# 1-Schematic_INFRARED_WAVER_V0_CHEAP.net
KiCad netlist of a schematic drawn in EasyEDA
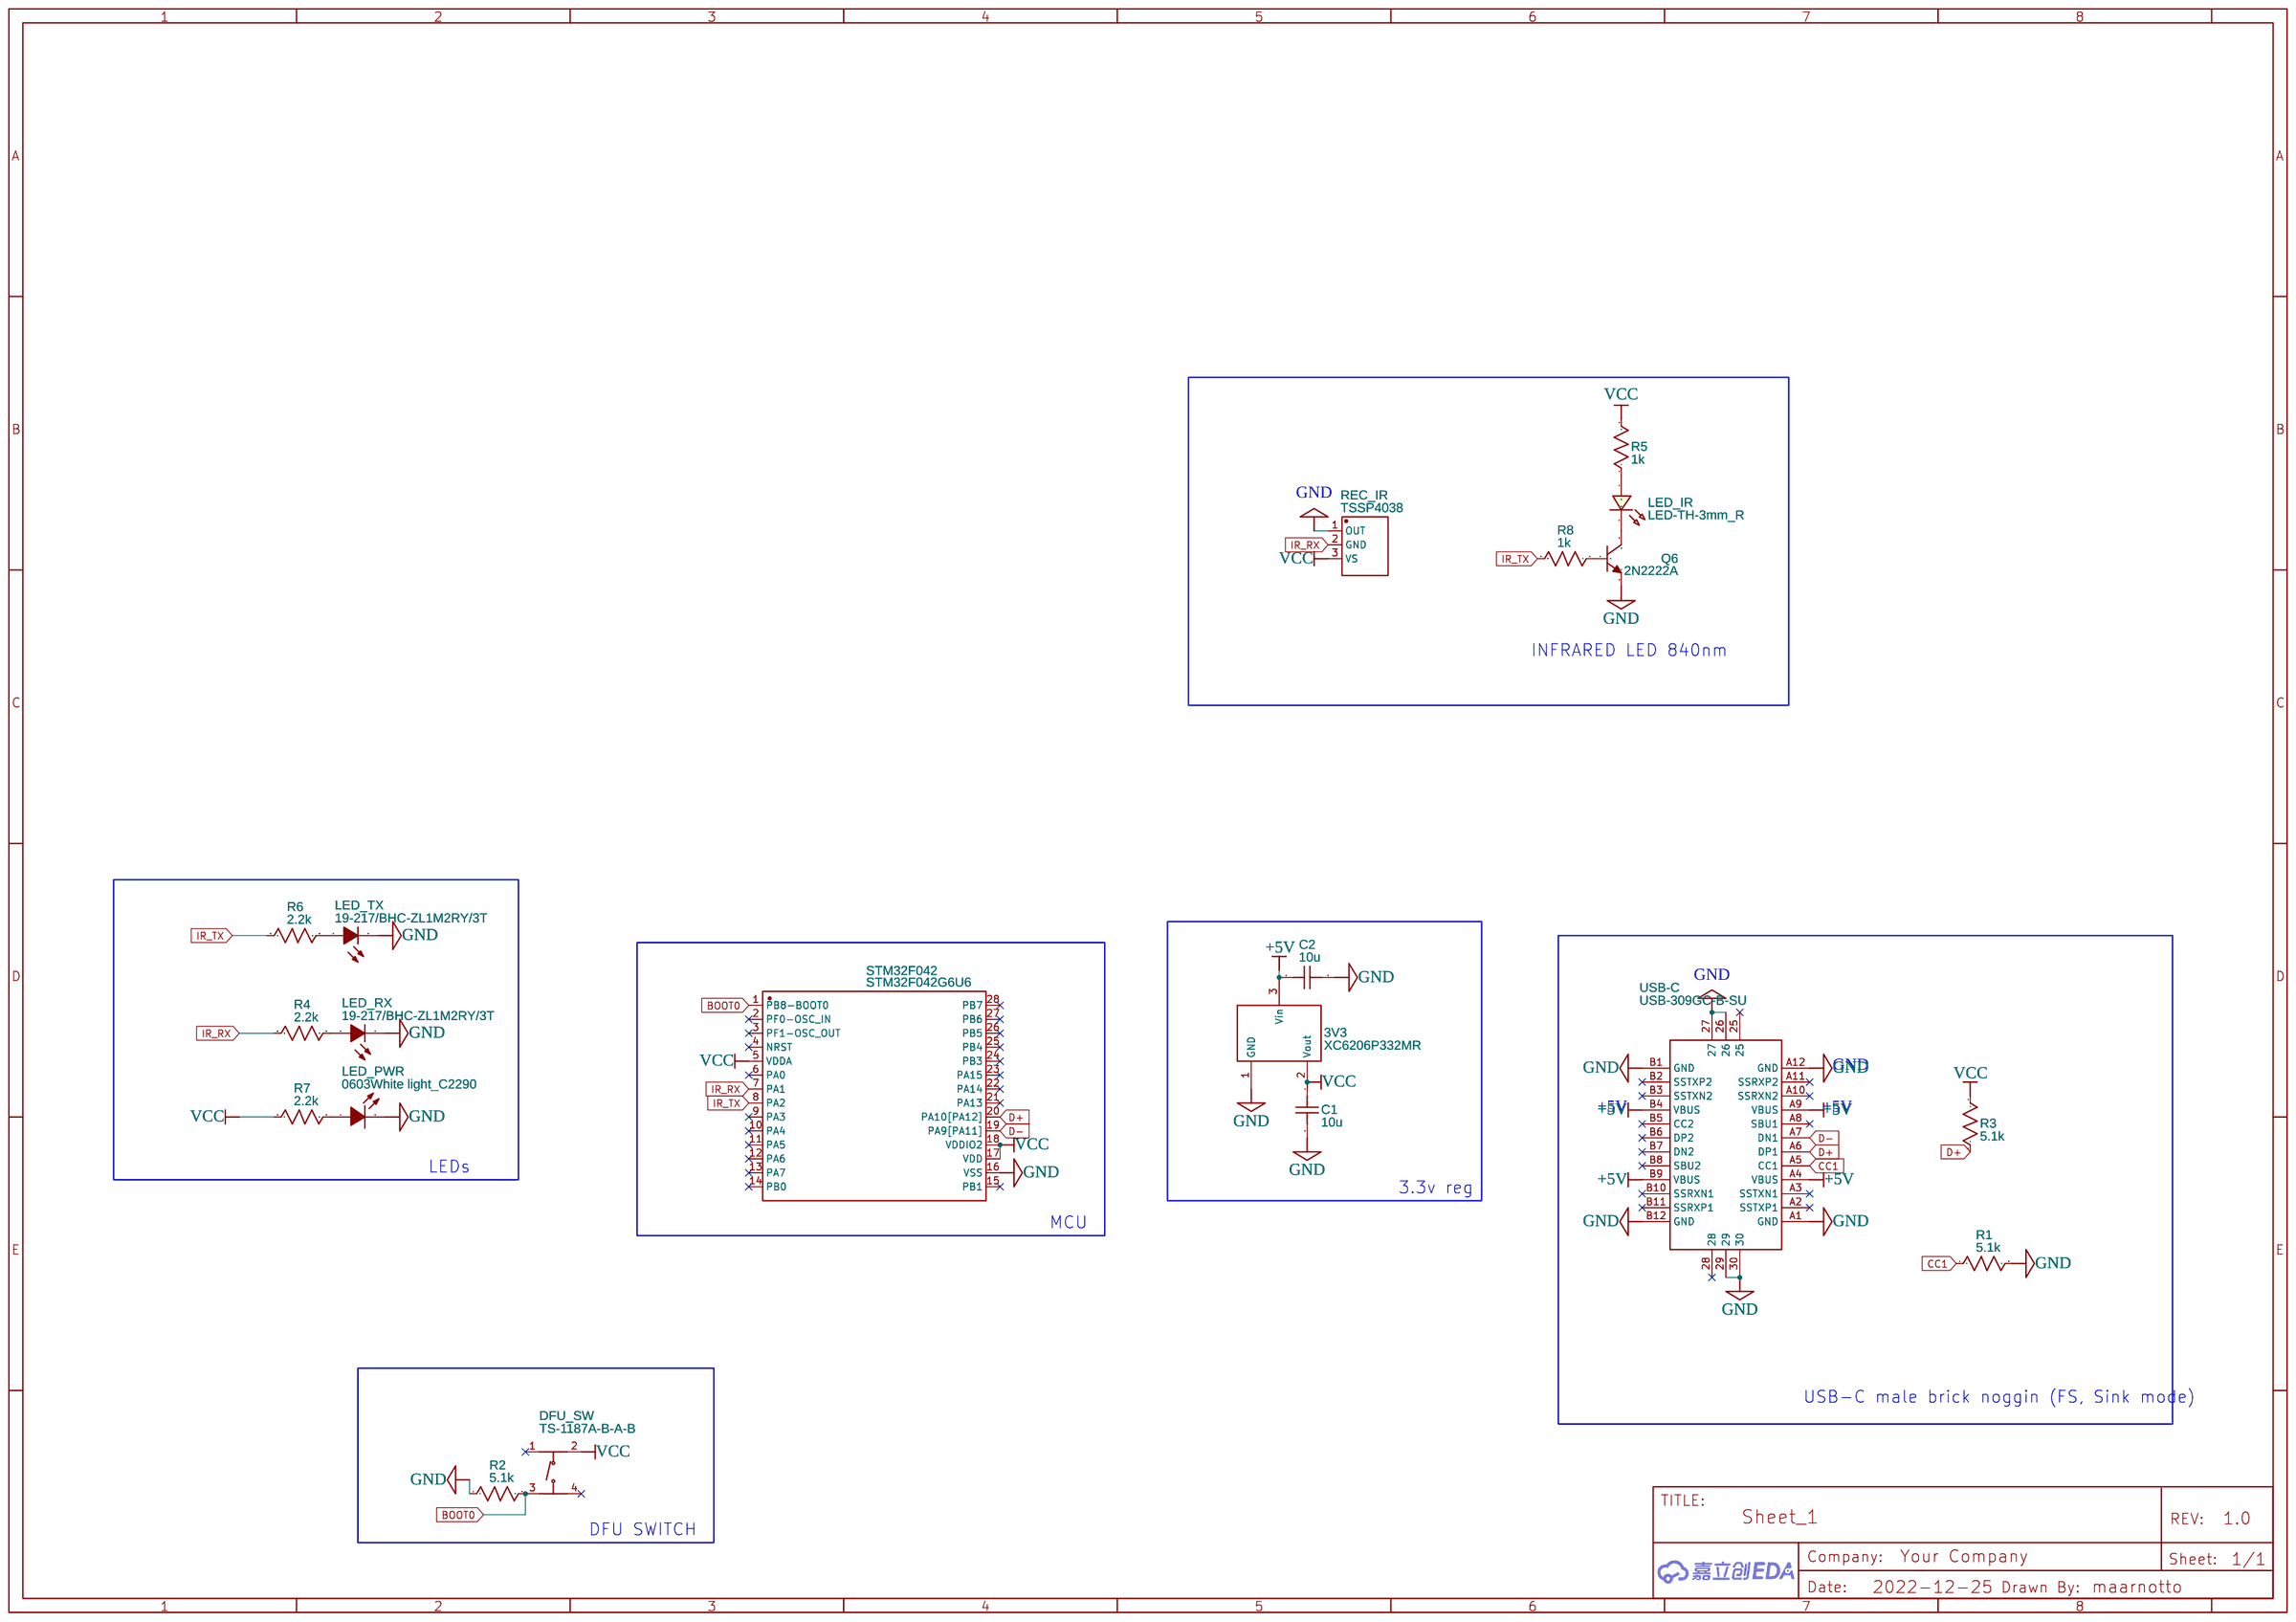
[diagram p0: schematic sheet]

(export (version "E")
  (design (tool "Eeschema 10.0.6"))
  (components
    (comp (ref "3V3")
      (value "XC6206P332MR")
      (fields (field (name "Manufacturer") "TOREX(特瑞仕)"))
      (libsource (lib "") (part "XC6206P332MR"))
    )
    (comp (ref "C1") (value "10u") (libsource (lib "") (part "C_0603_US")))
    (comp (ref "C2") (value "10u") (libsource (lib "") (part "C_0603_US_1")))
    (comp (ref "DFU_SW")
      (value "TS-1187A-B-A-B")
      (fields (field (name "Manufacturer") "XKB Connectivity(中国星坤)"))
      (libsource (lib "") (part "TS-1187A-B-A-B"))
    )
    (comp (ref "LED_IR")
      (value "LED-TH-3mm_R")
      (fields
        (field (name "Manufacturer Part") "204-10SDRD/S530-A3-L")
        (field (name "Manufacturer") "EVERLIGHT(台湾亿光)")
      )
      (libsource (lib "") (part "LED-TH-3mm_R"))
    )
    (comp (ref "LED_PWR")
      (value "0603White light_C2290")
      (fields (field (name "Manufacturer Part") "KT-0603白灯"))
      (libsource (lib "") (part "0603White light_C2290"))
    )
    (comp (ref "LED_RX")
      (value "19-217/BHC-ZL1M2RY/3T")
      (fields (field (name "Manufacturer") "EVERLIGHT(亿光)"))
      (libsource (lib "") (part "19-217/BHC-ZL1M2RY/3T_1"))
    )
    (comp (ref "LED_TX")
      (value "19-217/BHC-ZL1M2RY/3T")
      (fields (field (name "Manufacturer") "EVERLIGHT(亿光)"))
      (libsource (lib "") (part "19-217/BHC-ZL1M2RY/3T"))
    )
    (comp (ref "Q6")
      (value "2N2222A")
      (fields (field (name "Manufacturer") "BLUE ROCKET(蓝箭)"))
      (libsource (lib "") (part "2N2222A"))
    )
    (comp (ref "R1") (value "5.1k") (libsource (lib "") (part "R_0603_US")))
    (comp (ref "R2") (value "5.1k") (libsource (lib "") (part "R_0603_US")))
    (comp (ref "R3") (value "5.1k") (libsource (lib "") (part "R_0603_US_1")))
    (comp (ref "R4") (value "2.2k") (libsource (lib "") (part "R_0603_US")))
    (comp (ref "R5") (value "1k") (libsource (lib "") (part "R_AXIAL-0.3_US")))
    (comp (ref "R6") (value "2.2k") (libsource (lib "") (part "R_0603_US")))
    (comp (ref "R7") (value "2.2k") (libsource (lib "") (part "R_0603_US")))
    (comp (ref "R8") (value "1k") (libsource (lib "") (part "R_AXIAL-0.3_US_1")))
    (comp (ref "REC_IR")
      (value "TSSP4038")
      (fields (field (name "Manufacturer") "VISHAY(威世)"))
      (libsource (lib "") (part "TSSP4038"))
    )
    (comp (ref "STM32F042")
      (value "STM32F042G6U6")
      (fields (field (name "Manufacturer") "ST(意法半导体)"))
      (libsource (lib "") (part "STM32F042G6U6"))
    )
    (comp (ref "USB-C")
      (value "USB-309GC-B-SU")
      (fields (field (name "Manufacturer") "HOOYA"))
      (libsource (lib "") (part "USB-309GC-B-SU"))
    )
  )
  (nets
    (net (code "1") (name "+5V") (class "Default")
      (node (ref "3V3") (pin "3") (pinfunction "Vin_3") (pintype "unspecified"))
      (node (ref "C2") (pin "2") (pinfunction "2_2") (pintype "unspecified"))
      (node (ref "USB-C") (pin "A4") (pinfunction "VBUS_A4") (pintype "unspecified"))
      (node (ref "USB-C") (pin "A9") (pinfunction "VBUS_A9") (pintype "unspecified"))
      (node (ref "USB-C") (pin "B4") (pinfunction "VBUS_B4") (pintype "unspecified"))
      (node (ref "USB-C") (pin "B9") (pinfunction "VBUS_B9") (pintype "unspecified"))
    )
    (net (code "2") (name "BOOT0") (class "Default")
      (node (ref "DFU_SW") (pin "3") (pinfunction "C_3") (pintype "unspecified"))
      (node (ref "R2") (pin "2") (pinfunction "2_2") (pintype "unspecified"))
      (node (ref "STM32F042") (pin "1") (pinfunction "PB8-BOOT0_1") (pintype "unspecified"))
    )
    (net (code "3") (name "CC1") (class "Default")
      (node (ref "R1") (pin "1") (pinfunction "1_1") (pintype "unspecified"))
      (node (ref "USB-C") (pin "A5") (pinfunction "CC1_A5") (pintype "unspecified"))
    )
    (net (code "4") (name "D+") (class "Default")
      (node (ref "R3") (pin "2") (pinfunction "2_2") (pintype "unspecified"))
      (node (ref "STM32F042") (pin "20") (pinfunction "PA10[PA12]_20") (pintype "unspecified"))
      (node (ref "USB-C") (pin "A6") (pinfunction "DP1_A6") (pintype "unspecified"))
    )
    (net (code "5") (name "D-") (class "Default")
      (node (ref "STM32F042") (pin "19") (pinfunction "PA9[PA11]_19") (pintype "unspecified"))
      (node (ref "USB-C") (pin "A7") (pinfunction "DN1_A7") (pintype "unspecified"))
    )
    (net (code "6") (name "GND") (class "Default")
      (node (ref "3V3") (pin "1") (pinfunction "GND_1") (pintype "unspecified"))
      (node (ref "C1") (pin "2") (pinfunction "2_2") (pintype "unspecified"))
      (node (ref "C2") (pin "1") (pinfunction "1_1") (pintype "unspecified"))
      (node (ref "LED_PWR") (pin "2") (pinfunction "K_2") (pintype "unspecified"))
      (node (ref "LED_RX") (pin "1") (pinfunction "C_1") (pintype "input"))
      (node (ref "LED_TX") (pin "1") (pinfunction "C_1") (pintype "input"))
      (node (ref "Q6") (pin "3") (pinfunction "E_3") (pintype "unspecified"))
      (node (ref "R1") (pin "2") (pinfunction "2_2") (pintype "unspecified"))
      (node (ref "R2") (pin "1") (pinfunction "1_1") (pintype "unspecified"))
      (node (ref "REC_IR") (pin "1") (pinfunction "OUT_1") (pintype "unspecified"))
      (node (ref "STM32F042") (pin "16") (pinfunction "VSS_16") (pintype "unspecified"))
      (node (ref "USB-C") (pin "26") (pinfunction "26_26") (pintype "unspecified"))
      (node (ref "USB-C") (pin "27") (pinfunction "27_27") (pintype "unspecified"))
      (node (ref "USB-C") (pin "29") (pinfunction "29_29") (pintype "unspecified"))
      (node (ref "USB-C") (pin "30") (pinfunction "30_30") (pintype "unspecified"))
      (node (ref "USB-C") (pin "A1") (pinfunction "GND_A1") (pintype "unspecified"))
      (node (ref "USB-C") (pin "A12") (pinfunction "GND_A12") (pintype "unspecified"))
      (node (ref "USB-C") (pin "B1") (pinfunction "GND_B1") (pintype "unspecified"))
      (node (ref "USB-C") (pin "B12") (pinfunction "GND_B12") (pintype "unspecified"))
    )
    (net (code "7") (name "IR_RX") (class "Default")
      (node (ref "R4") (pin "1") (pinfunction "1_1") (pintype "unspecified"))
      (node (ref "REC_IR") (pin "2") (pinfunction "GND_2") (pintype "unspecified"))
      (node (ref "STM32F042") (pin "7") (pinfunction "PA1_7") (pintype "unspecified"))
    )
    (net (code "8") (name "IR_TX") (class "Default")
      (node (ref "R6") (pin "1") (pinfunction "1_1") (pintype "unspecified"))
      (node (ref "R8") (pin "2") (pinfunction "2_2") (pintype "unspecified"))
      (node (ref "STM32F042") (pin "8") (pinfunction "PA2_8") (pintype "unspecified"))
    )
    (net (code "9") (name "Net-(LED_IR-Pad1)") (class "Default")
      (node (ref "LED_IR") (pin "1") (pinfunction "1_1") (pintype "unspecified"))
      (node (ref "R5") (pin "1") (pinfunction "1_1") (pintype "unspecified"))
    )
    (net (code "10") (name "Net-(LED_PWR-A)") (class "Default")
      (node (ref "LED_PWR") (pin "1") (pinfunction "A_1") (pintype "unspecified"))
      (node (ref "R7") (pin "2") (pinfunction "2_2") (pintype "unspecified"))
    )
    (net (code "11") (name "Net-(LED_RX-A)") (class "Default")
      (node (ref "LED_RX") (pin "2") (pinfunction "A_2") (pintype "input"))
      (node (ref "R4") (pin "2") (pinfunction "2_2") (pintype "unspecified"))
    )
    (net (code "12") (name "Net-(LED_TX-A)") (class "Default")
      (node (ref "LED_TX") (pin "2") (pinfunction "A_2") (pintype "input"))
      (node (ref "R6") (pin "2") (pinfunction "2_2") (pintype "unspecified"))
    )
    (net (code "13") (name "Net-(Q6-B)") (class "Default")
      (node (ref "Q6") (pin "2") (pinfunction "B_2") (pintype "unspecified"))
      (node (ref "R8") (pin "1") (pinfunction "1_1") (pintype "unspecified"))
    )
    (net (code "14") (name "Net-(Q6-C)") (class "Default")
      (node (ref "LED_IR") (pin "2") (pinfunction "2_2") (pintype "unspecified"))
      (node (ref "Q6") (pin "1") (pinfunction "C_1") (pintype "unspecified"))
    )
    (net (code "15") (name "VCC") (class "Default")
      (node (ref "3V3") (pin "2") (pinfunction "Vout_2") (pintype "unspecified"))
      (node (ref "C1") (pin "1") (pinfunction "1_1") (pintype "unspecified"))
      (node (ref "DFU_SW") (pin "2") (pinfunction "B_2") (pintype "unspecified"))
      (node (ref "R3") (pin "1") (pinfunction "1_1") (pintype "unspecified"))
      (node (ref "R5") (pin "2") (pinfunction "2_2") (pintype "unspecified"))
      (node (ref "R7") (pin "1") (pinfunction "1_1") (pintype "unspecified"))
      (node (ref "REC_IR") (pin "3") (pinfunction "VS_3") (pintype "unspecified"))
      (node (ref "STM32F042") (pin "17") (pinfunction "VDD_17") (pintype "unspecified"))
      (node (ref "STM32F042") (pin "18") (pinfunction "VDDIO2_18") (pintype "unspecified"))
      (node (ref "STM32F042") (pin "5") (pinfunction "VDDA_5") (pintype "unspecified"))
    )
    (net (code "16") (name "unconnected-(DFU_SW-A-Pad1)") (class "Default")
      (node (ref "DFU_SW") (pin "1") (pinfunction "A_1") (pintype "unspecified+no_connect"))
    )
    (net (code "17") (name "unconnected-(DFU_SW-D-Pad4)") (class "Default")
      (node (ref "DFU_SW") (pin "4") (pinfunction "D_4") (pintype "unspecified+no_connect"))
    )
    (net (code "18") (name "unconnected-(STM32F042-NRST-Pad4)") (class "Default")
      (node (ref "STM32F042") (pin "4") (pinfunction "NRST_4") (pintype "unspecified+no_connect"))
    )
    (net (code "19") (name "unconnected-(STM32F042-PA0-Pad6)") (class "Default")
      (node (ref "STM32F042") (pin "6") (pinfunction "PA0_6") (pintype "unspecified+no_connect"))
    )
    (net (code "20") (name "unconnected-(STM32F042-PA3-Pad9)") (class "Default")
      (node (ref "STM32F042") (pin "9") (pinfunction "PA3_9") (pintype "unspecified+no_connect"))
    )
    (net (code "21") (name "unconnected-(STM32F042-PA4-Pad10)") (class "Default")
      (node (ref "STM32F042") (pin "10") (pinfunction "PA4_10") (pintype "unspecified+no_connect"))
    )
    (net (code "22") (name "unconnected-(STM32F042-PA5-Pad11)") (class "Default")
      (node (ref "STM32F042") (pin "11") (pinfunction "PA5_11") (pintype "unspecified+no_connect"))
    )
    (net (code "23") (name "unconnected-(STM32F042-PA6-Pad12)") (class "Default")
      (node (ref "STM32F042") (pin "12") (pinfunction "PA6_12") (pintype "unspecified+no_connect"))
    )
    (net (code "24") (name "unconnected-(STM32F042-PA7-Pad13)") (class "Default")
      (node (ref "STM32F042") (pin "13") (pinfunction "PA7_13") (pintype "unspecified+no_connect"))
    )
    (net (code "25") (name "unconnected-(STM32F042-PA13-Pad21)") (class "Default")
      (node (ref "STM32F042") (pin "21") (pinfunction "PA13_21") (pintype "unspecified+no_connect"))
    )
    (net (code "26") (name "unconnected-(STM32F042-PA14-Pad22)") (class "Default")
      (node (ref "STM32F042") (pin "22") (pinfunction "PA14_22") (pintype "unspecified+no_connect"))
    )
    (net (code "27") (name "unconnected-(STM32F042-PA15-Pad23)") (class "Default")
      (node (ref "STM32F042") (pin "23") (pinfunction "PA15_23") (pintype "unspecified+no_connect"))
    )
    (net (code "28") (name "unconnected-(STM32F042-PB0-Pad14)") (class "Default")
      (node (ref "STM32F042") (pin "14") (pinfunction "PB0_14") (pintype "unspecified+no_connect"))
    )
    (net (code "29") (name "unconnected-(STM32F042-PB1-Pad15)") (class "Default")
      (node (ref "STM32F042") (pin "15") (pinfunction "PB1_15") (pintype "unspecified+no_connect"))
    )
    (net (code "30") (name "unconnected-(STM32F042-PB3-Pad24)") (class "Default")
      (node (ref "STM32F042") (pin "24") (pinfunction "PB3_24") (pintype "unspecified+no_connect"))
    )
    (net (code "31") (name "unconnected-(STM32F042-PB4-Pad25)") (class "Default")
      (node (ref "STM32F042") (pin "25") (pinfunction "PB4_25") (pintype "unspecified+no_connect"))
    )
    (net (code "32") (name "unconnected-(STM32F042-PB5-Pad26)") (class "Default")
      (node (ref "STM32F042") (pin "26") (pinfunction "PB5_26") (pintype "unspecified+no_connect"))
    )
    (net (code "33") (name "unconnected-(STM32F042-PB6-Pad27)") (class "Default")
      (node (ref "STM32F042") (pin "27") (pinfunction "PB6_27") (pintype "unspecified+no_connect"))
    )
    (net (code "34") (name "unconnected-(STM32F042-PB7-Pad28)") (class "Default")
      (node (ref "STM32F042") (pin "28") (pinfunction "PB7_28") (pintype "unspecified+no_connect"))
    )
    (net (code "35") (name "unconnected-(STM32F042-PF0-OSC_IN-Pad2)") (class "Default")
      (node (ref "STM32F042") (pin "2") (pinfunction "PF0-OSC_IN_2") (pintype "unspecified+no_connect"))
    )
    (net (code "36") (name "unconnected-(STM32F042-PF1-OSC_OUT-Pad3)") (class "Default")
      (node (ref "STM32F042") (pin "3") (pinfunction "PF1-OSC_OUT_3") (pintype "unspecified+no_connect"))
    )
    (net (code "37") (name "unconnected-(USB-C-CC2-PadB5)") (class "Default")
      (node (ref "USB-C") (pin "B5") (pinfunction "CC2_B5") (pintype "unspecified+no_connect"))
    )
    (net (code "38") (name "unconnected-(USB-C-DN2-PadB7)") (class "Default")
      (node (ref "USB-C") (pin "B7") (pinfunction "DN2_B7") (pintype "unspecified+no_connect"))
    )
    (net (code "39") (name "unconnected-(USB-C-DP2-PadB6)") (class "Default")
      (node (ref "USB-C") (pin "B6") (pinfunction "DP2_B6") (pintype "unspecified+no_connect"))
    )
    (net (code "40") (name "unconnected-(USB-C-Pad25)") (class "Default")
      (node (ref "USB-C") (pin "25") (pinfunction "25_25") (pintype "unspecified+no_connect"))
    )
    (net (code "41") (name "unconnected-(USB-C-Pad28)") (class "Default")
      (node (ref "USB-C") (pin "28") (pinfunction "28_28") (pintype "unspecified+no_connect"))
    )
    (net (code "42") (name "unconnected-(USB-C-SBU1-PadA8)") (class "Default")
      (node (ref "USB-C") (pin "A8") (pinfunction "SBU1_A8") (pintype "unspecified+no_connect"))
    )
    (net (code "43") (name "unconnected-(USB-C-SBU2-PadB8)") (class "Default")
      (node (ref "USB-C") (pin "B8") (pinfunction "SBU2_B8") (pintype "unspecified+no_connect"))
    )
    (net (code "44") (name "unconnected-(USB-C-SSRXN1-PadB10)") (class "Default")
      (node (ref "USB-C") (pin "B10") (pinfunction "SSRXN1_B10") (pintype "unspecified+no_connect"))
    )
    (net (code "45") (name "unconnected-(USB-C-SSRXN2-PadA10)") (class "Default")
      (node (ref "USB-C") (pin "A10") (pinfunction "SSRXN2_A10") (pintype "unspecified+no_connect"))
    )
    (net (code "46") (name "unconnected-(USB-C-SSRXP1-PadB11)") (class "Default")
      (node (ref "USB-C") (pin "B11") (pinfunction "SSRXP1_B11") (pintype "unspecified+no_connect"))
    )
    (net (code "47") (name "unconnected-(USB-C-SSRXP2-PadA11)") (class "Default")
      (node (ref "USB-C") (pin "A11") (pinfunction "SSRXP2_A11") (pintype "unspecified+no_connect"))
    )
    (net (code "48") (name "unconnected-(USB-C-SSTXN1-PadA3)") (class "Default")
      (node (ref "USB-C") (pin "A3") (pinfunction "SSTXN1_A3") (pintype "unspecified+no_connect"))
    )
    (net (code "49") (name "unconnected-(USB-C-SSTXN2-PadB3)") (class "Default")
      (node (ref "USB-C") (pin "B3") (pinfunction "SSTXN2_B3") (pintype "unspecified+no_connect"))
    )
    (net (code "50") (name "unconnected-(USB-C-SSTXP1-PadA2)") (class "Default")
      (node (ref "USB-C") (pin "A2") (pinfunction "SSTXP1_A2") (pintype "unspecified+no_connect"))
    )
    (net (code "51") (name "unconnected-(USB-C-SSTXP2-PadB2)") (class "Default")
      (node (ref "USB-C") (pin "B2") (pinfunction "SSTXP2_B2") (pintype "unspecified+no_connect"))
    )
  )
)
